# VU_Meter_Featherwing.net
KiCad netlist of a schematic drawn in EAGLE
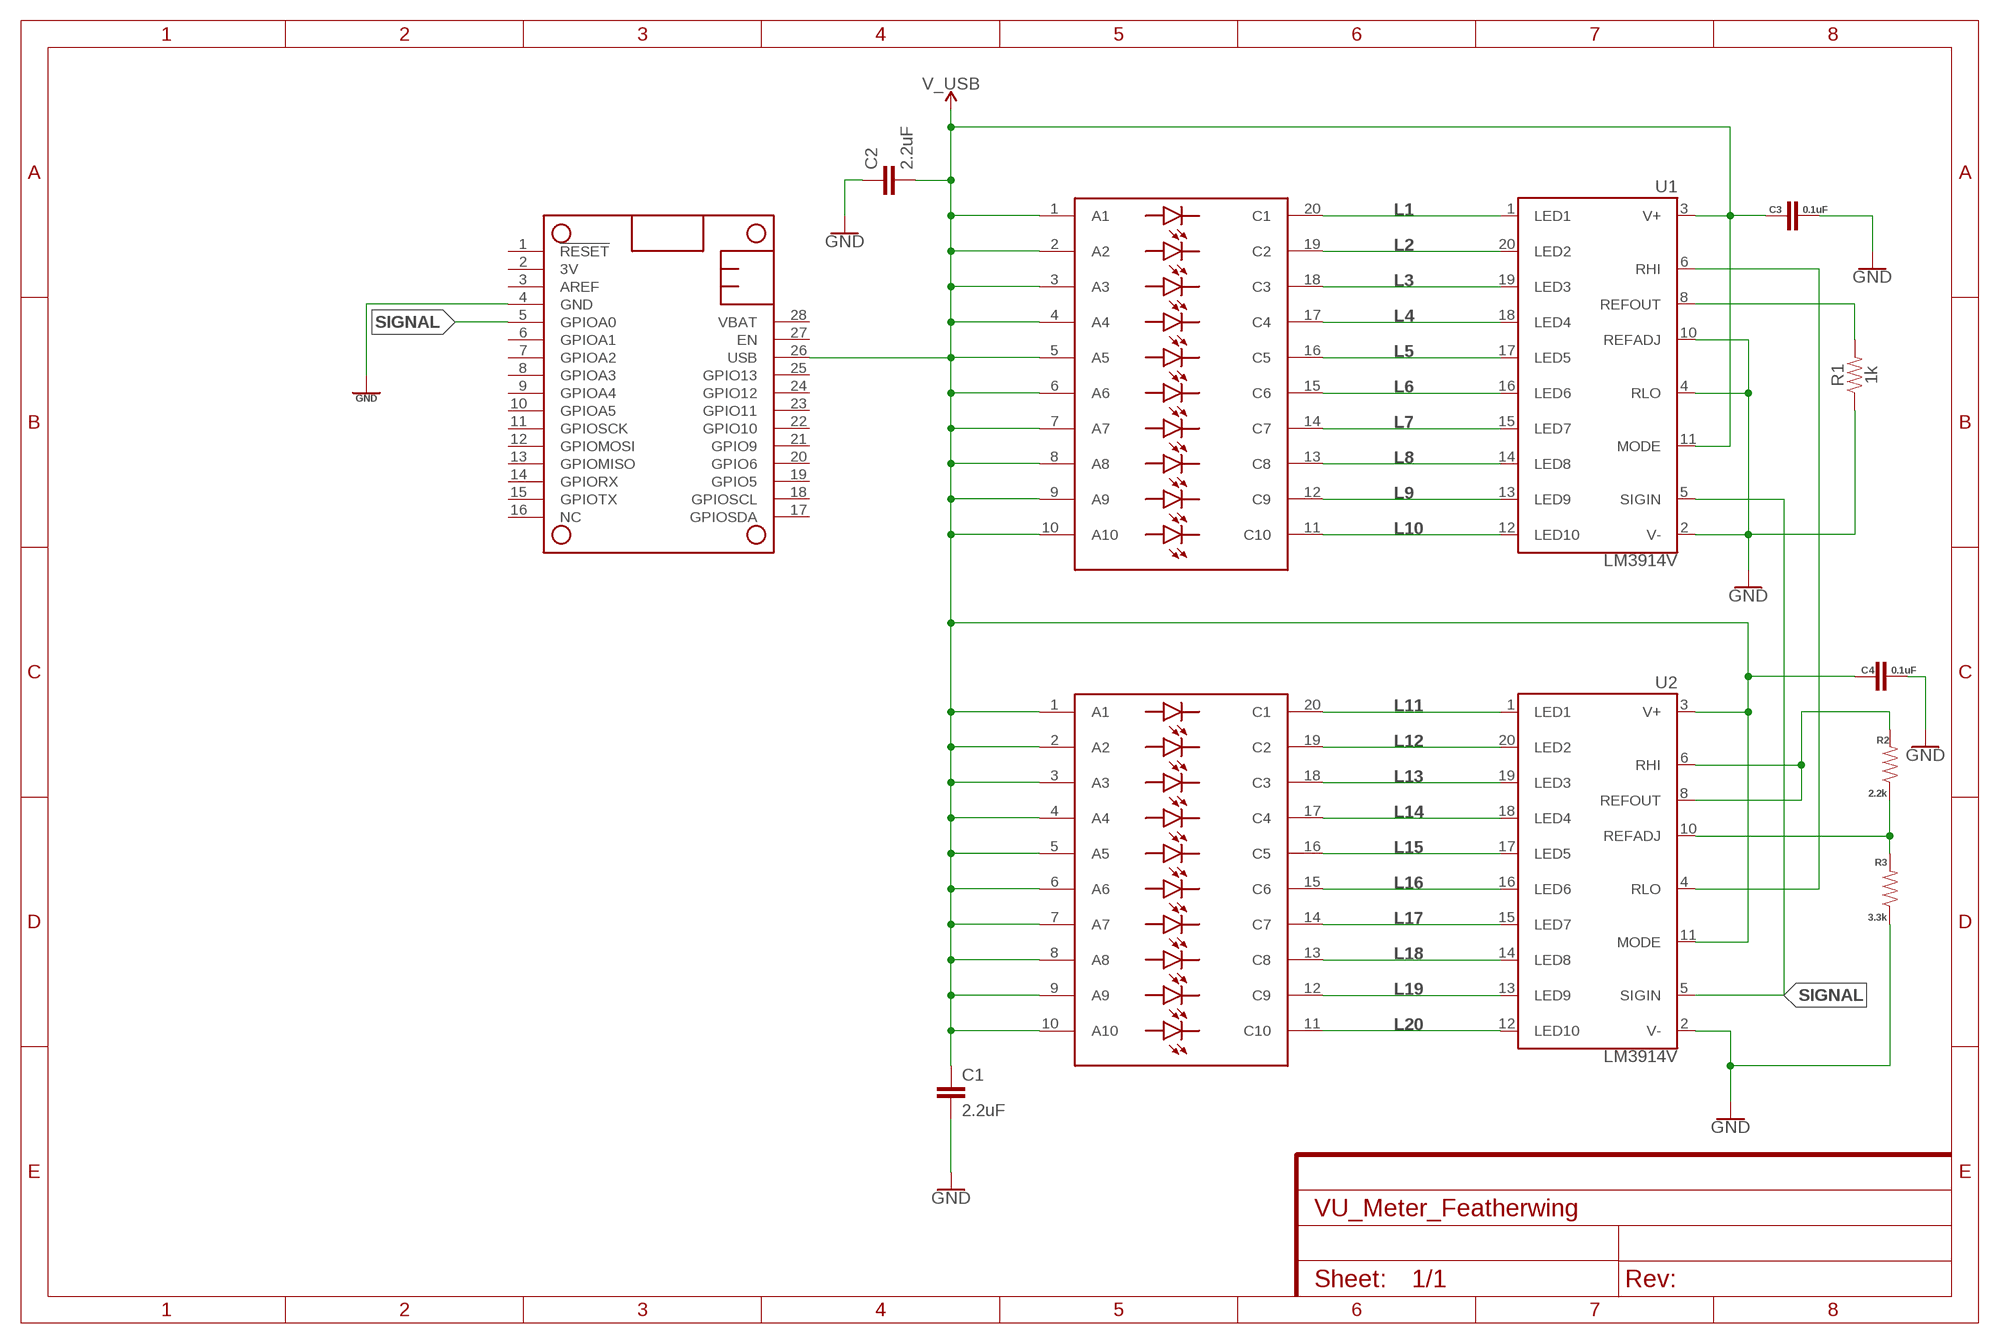
[diagram p0: schematic, sheet 1]

(export (version "E")
  (design (tool "Eeschema 10.0.6"))
  (components
    (comp (ref "C1")
      (value "2.2uF")
      (footprint "eagle-import:0603")
      (libsource (lib "eagle-import") (part "2.2UF-0603-10V-20%"))
    )
    (comp (ref "C2")
      (value "2.2uF")
      (footprint "eagle-import:0603")
      (libsource (lib "eagle-import") (part "2.2UF-0603-10V-20%"))
    )
    (comp (ref "C3")
      (value "0.1uF")
      (footprint "eagle-import:0603")
      (libsource (lib "eagle-import") (part "0.1UF-0603-25V-(+80/-20%)"))
    )
    (comp (ref "C4")
      (value "0.1uF")
      (footprint "eagle-import:0603")
      (libsource (lib "eagle-import") (part "0.1UF-0603-25V-(+80/-20%)"))
    )
    (comp (ref "MS1")
      (value "FEATHERWINGBAR_GRAPH")
      (footprint "eagle-import:FEATHERWING_BAR")
      (libsource (lib "eagle-import") (part "FEATHERWINGBAR_GRAPH"))
    )
    (comp (ref "R1")
      (value "1k")
      (footprint "eagle-import:0603")
      (libsource (lib "eagle-import") (part "1KOHM-0603-1/10W-1%"))
    )
    (comp (ref "R2")
      (value "2.2k")
      (footprint "eagle-import:0603")
      (libsource (lib "eagle-import") (part "2.2KOHM-0603-1/10W-1%"))
    )
    (comp (ref "R3")
      (value "3.3k")
      (footprint "eagle-import:0603")
      (libsource (lib "eagle-import") (part "3.3KOHM-0603-1/10W-1%"))
    )
    (comp (ref "U$1")
      (value "BAR_GRAPHSMD-BARGRAPH")
      (footprint "eagle-import:3104310541105000")
      (libsource (lib "eagle-import") (part "BAR_GRAPHSMD-BARGRAPH"))
    )
    (comp (ref "U$2")
      (value "BAR_GRAPHSMD-BARGRAPH")
      (footprint "eagle-import:3104310541105000")
      (libsource (lib "eagle-import") (part "BAR_GRAPHSMD-BARGRAPH"))
    )
    (comp (ref "U1")
      (value "LM3914V")
      (footprint "eagle-import:PLCC20S")
      (libsource (lib "eagle-import") (part "LM391V4"))
    )
    (comp (ref "U2")
      (value "LM3914V")
      (footprint "eagle-import:PLCC20S")
      (libsource (lib "eagle-import") (part "LM391V4"))
    )
  )
  (nets
    (net (code "1") (name "/3V") (class "Default")
      (node (ref "MS1") (pin "2") (pinfunction "3V_2") (pintype "power_in"))
    )
    (net (code "2") (name "/L1") (class "Default")
      (node (ref "U$1") (pin "20") (pinfunction "C1_20") (pintype "bidirectional"))
      (node (ref "U1") (pin "1") (pinfunction "LED1_1") (pintype "output"))
    )
    (net (code "3") (name "/L2") (class "Default")
      (node (ref "U$1") (pin "19") (pinfunction "C2_19") (pintype "bidirectional"))
      (node (ref "U1") (pin "20") (pinfunction "LED2_20") (pintype "output"))
    )
    (net (code "4") (name "/L3") (class "Default")
      (node (ref "U$1") (pin "18") (pinfunction "C3_18") (pintype "bidirectional"))
      (node (ref "U1") (pin "19") (pinfunction "LED3_19") (pintype "output"))
    )
    (net (code "5") (name "/L4") (class "Default")
      (node (ref "U$1") (pin "17") (pinfunction "C4_17") (pintype "bidirectional"))
      (node (ref "U1") (pin "18") (pinfunction "LED4_18") (pintype "output"))
    )
    (net (code "6") (name "/L5") (class "Default")
      (node (ref "U$1") (pin "16") (pinfunction "C5_16") (pintype "bidirectional"))
      (node (ref "U1") (pin "17") (pinfunction "LED5_17") (pintype "output"))
    )
    (net (code "7") (name "/L6") (class "Default")
      (node (ref "U$1") (pin "15") (pinfunction "C6_15") (pintype "bidirectional"))
      (node (ref "U1") (pin "16") (pinfunction "LED6_16") (pintype "output"))
    )
    (net (code "8") (name "/L7") (class "Default")
      (node (ref "U$1") (pin "14") (pinfunction "C7_14") (pintype "bidirectional"))
      (node (ref "U1") (pin "15") (pinfunction "LED7_15") (pintype "output"))
    )
    (net (code "9") (name "/L8") (class "Default")
      (node (ref "U$1") (pin "13") (pinfunction "C8_13") (pintype "bidirectional"))
      (node (ref "U1") (pin "14") (pinfunction "LED8_14") (pintype "output"))
    )
    (net (code "10") (name "/L9") (class "Default")
      (node (ref "U$1") (pin "12") (pinfunction "C9_12") (pintype "bidirectional"))
      (node (ref "U1") (pin "13") (pinfunction "LED9_13") (pintype "output"))
    )
    (net (code "11") (name "/L10") (class "Default")
      (node (ref "U$1") (pin "11") (pinfunction "C10_11") (pintype "bidirectional"))
      (node (ref "U1") (pin "12") (pinfunction "LED10_12") (pintype "output"))
    )
    (net (code "12") (name "/L11") (class "Default")
      (node (ref "U$2") (pin "20") (pinfunction "C1_20") (pintype "bidirectional"))
      (node (ref "U2") (pin "1") (pinfunction "LED1_1") (pintype "output"))
    )
    (net (code "13") (name "/L12") (class "Default")
      (node (ref "U$2") (pin "19") (pinfunction "C2_19") (pintype "bidirectional"))
      (node (ref "U2") (pin "20") (pinfunction "LED2_20") (pintype "output"))
    )
    (net (code "14") (name "/L13") (class "Default")
      (node (ref "U$2") (pin "18") (pinfunction "C3_18") (pintype "bidirectional"))
      (node (ref "U2") (pin "19") (pinfunction "LED3_19") (pintype "output"))
    )
    (net (code "15") (name "/L14") (class "Default")
      (node (ref "U$2") (pin "17") (pinfunction "C4_17") (pintype "bidirectional"))
      (node (ref "U2") (pin "18") (pinfunction "LED4_18") (pintype "output"))
    )
    (net (code "16") (name "/L15") (class "Default")
      (node (ref "U$2") (pin "16") (pinfunction "C5_16") (pintype "bidirectional"))
      (node (ref "U2") (pin "17") (pinfunction "LED5_17") (pintype "output"))
    )
    (net (code "17") (name "/L16") (class "Default")
      (node (ref "U$2") (pin "15") (pinfunction "C6_15") (pintype "bidirectional"))
      (node (ref "U2") (pin "16") (pinfunction "LED6_16") (pintype "output"))
    )
    (net (code "18") (name "/L17") (class "Default")
      (node (ref "U$2") (pin "14") (pinfunction "C7_14") (pintype "bidirectional"))
      (node (ref "U2") (pin "15") (pinfunction "LED7_15") (pintype "output"))
    )
    (net (code "19") (name "/L18") (class "Default")
      (node (ref "U$2") (pin "13") (pinfunction "C8_13") (pintype "bidirectional"))
      (node (ref "U2") (pin "14") (pinfunction "LED8_14") (pintype "output"))
    )
    (net (code "20") (name "/L19") (class "Default")
      (node (ref "U$2") (pin "12") (pinfunction "C9_12") (pintype "bidirectional"))
      (node (ref "U2") (pin "13") (pinfunction "LED9_13") (pintype "output"))
    )
    (net (code "21") (name "/L20") (class "Default")
      (node (ref "U$2") (pin "11") (pinfunction "C10_11") (pintype "bidirectional"))
      (node (ref "U2") (pin "12") (pinfunction "LED10_12") (pintype "output"))
    )
    (net (code "22") (name "/VBAT") (class "Default")
      (node (ref "MS1") (pin "28") (pinfunction "VBAT_28") (pintype "power_in"))
    )
    (net (code "23") (name "GND") (class "Default")
      (node (ref "C1") (pin "2") (pinfunction "2_2") (pintype "passive"))
      (node (ref "C2") (pin "1") (pinfunction "1_1") (pintype "passive"))
      (node (ref "C3") (pin "2") (pinfunction "2_2") (pintype "passive"))
      (node (ref "C4") (pin "2") (pinfunction "2_2") (pintype "passive"))
      (node (ref "MS1") (pin "4") (pinfunction "GND_4") (pintype "power_in"))
      (node (ref "R1") (pin "1") (pinfunction "1_1") (pintype "passive"))
      (node (ref "R3") (pin "1") (pinfunction "1_1") (pintype "passive"))
      (node (ref "U1") (pin "10") (pinfunction "REFADJ_10") (pintype "passive"))
      (node (ref "U1") (pin "2") (pinfunction "V-_2") (pintype "power_in"))
      (node (ref "U1") (pin "4") (pinfunction "RLO_4") (pintype "input"))
      (node (ref "U2") (pin "2") (pinfunction "V-_2") (pintype "power_in"))
    )
    (net (code "24") (name "Net-(U1-REFOUT)") (class "Default")
      (node (ref "R1") (pin "2") (pinfunction "2_2") (pintype "passive"))
      (node (ref "U1") (pin "8") (pinfunction "REFOUT_8") (pintype "output"))
    )
    (net (code "25") (name "Net-(U1-RHI)") (class "Default")
      (node (ref "U1") (pin "6") (pinfunction "RHI_6") (pintype "input"))
      (node (ref "U2") (pin "4") (pinfunction "RLO_4") (pintype "input"))
    )
    (net (code "26") (name "Net-(U2-REFADJ)") (class "Default")
      (node (ref "R2") (pin "1") (pinfunction "1_1") (pintype "passive"))
      (node (ref "R3") (pin "2") (pinfunction "2_2") (pintype "passive"))
      (node (ref "U2") (pin "10") (pinfunction "REFADJ_10") (pintype "passive"))
    )
    (net (code "27") (name "Net-(U2-REFOUT)") (class "Default")
      (node (ref "R2") (pin "2") (pinfunction "2_2") (pintype "passive"))
      (node (ref "U2") (pin "6") (pinfunction "RHI_6") (pintype "input"))
      (node (ref "U2") (pin "8") (pinfunction "REFOUT_8") (pintype "output"))
    )
    (net (code "28") (name "SIGNAL") (class "Default")
      (node (ref "MS1") (pin "5") (pinfunction "GPIOA0_5") (pintype "bidirectional"))
      (node (ref "U1") (pin "5") (pinfunction "SIGIN_5") (pintype "input"))
      (node (ref "U2") (pin "5") (pinfunction "SIGIN_5") (pintype "input"))
    )
    (net (code "29") (name "V_USB") (class "Default")
      (node (ref "C1") (pin "1") (pinfunction "1_1") (pintype "passive"))
      (node (ref "C2") (pin "2") (pinfunction "2_2") (pintype "passive"))
      (node (ref "C3") (pin "1") (pinfunction "1_1") (pintype "passive"))
      (node (ref "C4") (pin "1") (pinfunction "1_1") (pintype "passive"))
      (node (ref "MS1") (pin "26") (pinfunction "USB_26") (pintype "power_in"))
      (node (ref "U$1") (pin "1") (pinfunction "A1_1") (pintype "bidirectional"))
      (node (ref "U$1") (pin "10") (pinfunction "A10_10") (pintype "bidirectional"))
      (node (ref "U$1") (pin "2") (pinfunction "A2_2") (pintype "bidirectional"))
      (node (ref "U$1") (pin "3") (pinfunction "A3_3") (pintype "bidirectional"))
      (node (ref "U$1") (pin "4") (pinfunction "A4_4") (pintype "bidirectional"))
      (node (ref "U$1") (pin "5") (pinfunction "A5_5") (pintype "bidirectional"))
      (node (ref "U$1") (pin "6") (pinfunction "A6_6") (pintype "bidirectional"))
      (node (ref "U$1") (pin "7") (pinfunction "A7_7") (pintype "bidirectional"))
      (node (ref "U$1") (pin "8") (pinfunction "A8_8") (pintype "bidirectional"))
      (node (ref "U$1") (pin "9") (pinfunction "A9_9") (pintype "bidirectional"))
      (node (ref "U$2") (pin "1") (pinfunction "A1_1") (pintype "bidirectional"))
      (node (ref "U$2") (pin "10") (pinfunction "A10_10") (pintype "bidirectional"))
      (node (ref "U$2") (pin "2") (pinfunction "A2_2") (pintype "bidirectional"))
      (node (ref "U$2") (pin "3") (pinfunction "A3_3") (pintype "bidirectional"))
      (node (ref "U$2") (pin "4") (pinfunction "A4_4") (pintype "bidirectional"))
      (node (ref "U$2") (pin "5") (pinfunction "A5_5") (pintype "bidirectional"))
      (node (ref "U$2") (pin "6") (pinfunction "A6_6") (pintype "bidirectional"))
      (node (ref "U$2") (pin "7") (pinfunction "A7_7") (pintype "bidirectional"))
      (node (ref "U$2") (pin "8") (pinfunction "A8_8") (pintype "bidirectional"))
      (node (ref "U$2") (pin "9") (pinfunction "A9_9") (pintype "bidirectional"))
      (node (ref "U1") (pin "11") (pinfunction "MODE_11") (pintype "input"))
      (node (ref "U1") (pin "3") (pinfunction "V+_3") (pintype "power_in"))
      (node (ref "U2") (pin "11") (pinfunction "MODE_11") (pintype "input"))
      (node (ref "U2") (pin "3") (pinfunction "V+_3") (pintype "power_in"))
    )
    (net (code "30") (name "unconnected-(MS1-AREF-Pad3)") (class "Default")
      (node (ref "MS1") (pin "3") (pinfunction "AREF_3") (pintype "passive"))
    )
    (net (code "31") (name "unconnected-(MS1-EN-Pad27)") (class "Default")
      (node (ref "MS1") (pin "27") (pinfunction "EN_27") (pintype "passive"))
    )
    (net (code "32") (name "unconnected-(MS1-GPIO5-Pad19)") (class "Default")
      (node (ref "MS1") (pin "19") (pinfunction "GPIO5_19") (pintype "bidirectional"))
    )
    (net (code "33") (name "unconnected-(MS1-GPIO6-Pad20)") (class "Default")
      (node (ref "MS1") (pin "20") (pinfunction "GPIO6_20") (pintype "bidirectional"))
    )
    (net (code "34") (name "unconnected-(MS1-GPIO9-Pad21)") (class "Default")
      (node (ref "MS1") (pin "21") (pinfunction "GPIO9_21") (pintype "bidirectional"))
    )
    (net (code "35") (name "unconnected-(MS1-GPIO10-Pad22)") (class "Default")
      (node (ref "MS1") (pin "22") (pinfunction "GPIO10_22") (pintype "bidirectional"))
    )
    (net (code "36") (name "unconnected-(MS1-GPIO11-Pad23)") (class "Default")
      (node (ref "MS1") (pin "23") (pinfunction "GPIO11_23") (pintype "bidirectional"))
    )
    (net (code "37") (name "unconnected-(MS1-GPIO12-Pad24)") (class "Default")
      (node (ref "MS1") (pin "24") (pinfunction "GPIO12_24") (pintype "bidirectional"))
    )
    (net (code "38") (name "unconnected-(MS1-GPIO13-Pad25)") (class "Default")
      (node (ref "MS1") (pin "25") (pinfunction "GPIO13_25") (pintype "bidirectional"))
    )
    (net (code "39") (name "unconnected-(MS1-GPIOA1-Pad6)") (class "Default")
      (node (ref "MS1") (pin "6") (pinfunction "GPIOA1_6") (pintype "bidirectional"))
    )
    (net (code "40") (name "unconnected-(MS1-GPIOA2-Pad7)") (class "Default")
      (node (ref "MS1") (pin "7") (pinfunction "GPIOA2_7") (pintype "bidirectional"))
    )
    (net (code "41") (name "unconnected-(MS1-GPIOA3-Pad8)") (class "Default")
      (node (ref "MS1") (pin "8") (pinfunction "GPIOA3_8") (pintype "bidirectional"))
    )
    (net (code "42") (name "unconnected-(MS1-GPIOA4-Pad9)") (class "Default")
      (node (ref "MS1") (pin "9") (pinfunction "GPIOA4_9") (pintype "bidirectional"))
    )
    (net (code "43") (name "unconnected-(MS1-GPIOA5-Pad10)") (class "Default")
      (node (ref "MS1") (pin "10") (pinfunction "GPIOA5_10") (pintype "bidirectional"))
    )
    (net (code "44") (name "unconnected-(MS1-GPIOMISO-Pad13)") (class "Default")
      (node (ref "MS1") (pin "13") (pinfunction "GPIOMISO_13") (pintype "bidirectional"))
    )
    (net (code "45") (name "unconnected-(MS1-GPIOMOSI-Pad12)") (class "Default")
      (node (ref "MS1") (pin "12") (pinfunction "GPIOMOSI_12") (pintype "bidirectional"))
    )
    (net (code "46") (name "unconnected-(MS1-GPIORX-Pad14)") (class "Default")
      (node (ref "MS1") (pin "14") (pinfunction "GPIORX_14") (pintype "bidirectional"))
    )
    (net (code "47") (name "unconnected-(MS1-GPIOSCK-Pad11)") (class "Default")
      (node (ref "MS1") (pin "11") (pinfunction "GPIOSCK_11") (pintype "bidirectional"))
    )
    (net (code "48") (name "unconnected-(MS1-GPIOSCL-Pad18)") (class "Default")
      (node (ref "MS1") (pin "18") (pinfunction "GPIOSCL_18") (pintype "bidirectional"))
    )
    (net (code "49") (name "unconnected-(MS1-GPIOSDA-Pad17)") (class "Default")
      (node (ref "MS1") (pin "17") (pinfunction "GPIOSDA_17") (pintype "bidirectional"))
    )
    (net (code "50") (name "unconnected-(MS1-GPIOTX-Pad15)") (class "Default")
      (node (ref "MS1") (pin "15") (pinfunction "GPIOTX_15") (pintype "bidirectional"))
    )
    (net (code "51") (name "unconnected-(MS1-NC-Pad16)") (class "Default")
      (node (ref "MS1") (pin "16") (pinfunction "NC_16") (pintype "passive"))
    )
    (net (code "52") (name "unconnected-(MS1-~{RESET}-Pad1)") (class "Default")
      (node (ref "MS1") (pin "1") (pinfunction "~{RESET}_1") (pintype "input"))
    )
  )
)
